# Laser_Array_CPU_V1_1.net
KiCad netlist of a schematic drawn in EAGLE
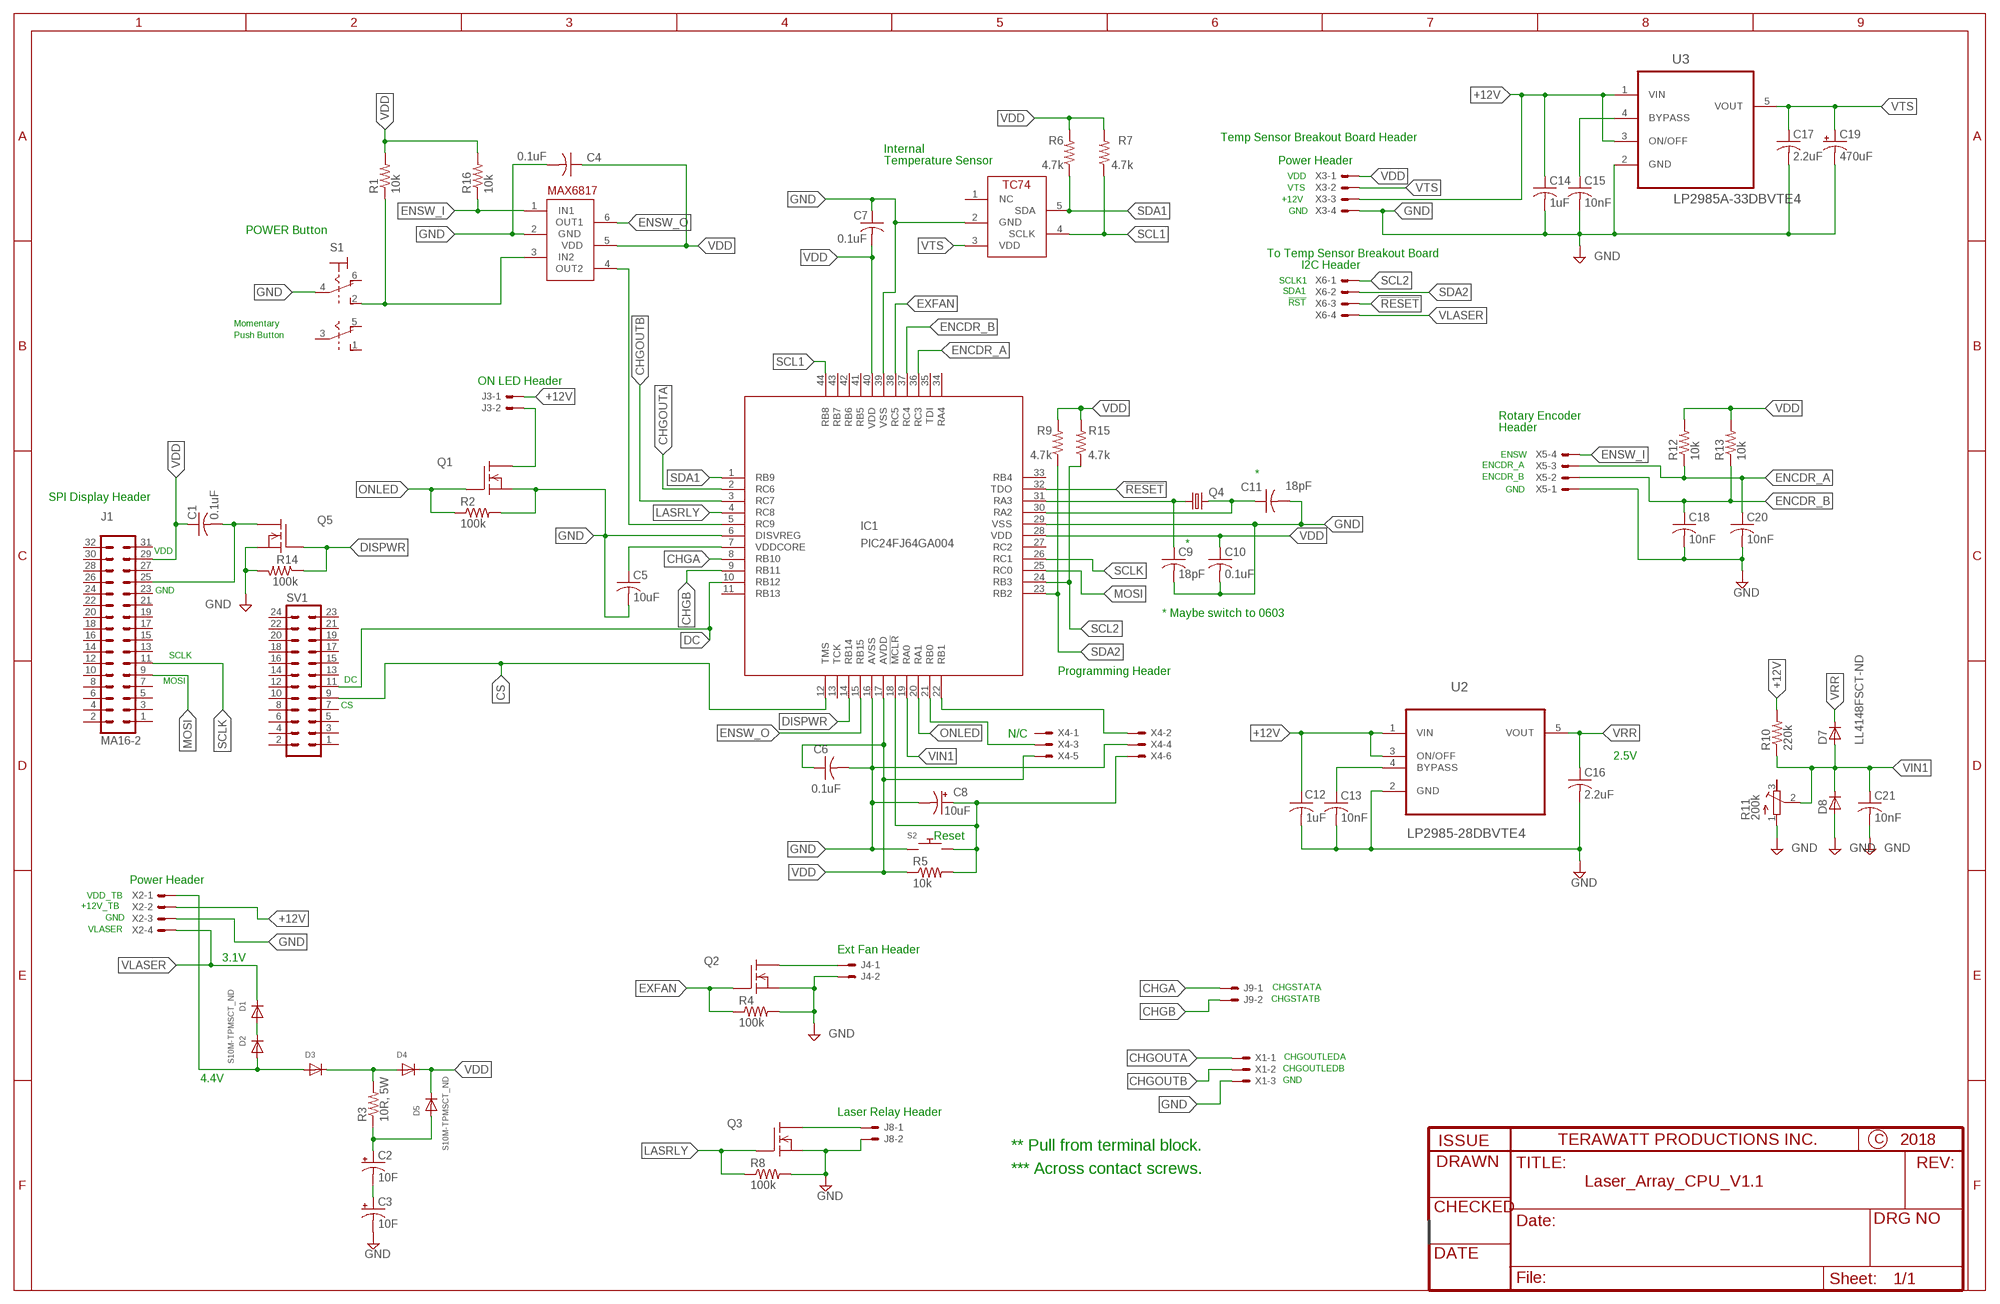
[diagram p0: schematic, sheet 1]

(export (version "E")
  (design (tool "Eeschema 10.0.6"))
  (components
    (comp (ref "C1")
      (value "0.1uF")
      (footprint "eagle-import:C0805")
      (libsource (lib "eagle-import") (part "C-USC0805"))
    )
    (comp (ref "C2")
      (value "10F")
      (footprint "eagle-import:E5-10,5")
      (libsource (lib "eagle-import") (part "CPOL-USE5-10.5"))
    )
    (comp (ref "C3")
      (value "10F")
      (footprint "eagle-import:E5-10,5")
      (libsource (lib "eagle-import") (part "CPOL-USE5-10.5"))
    )
    (comp (ref "C4")
      (value "0.1uF")
      (footprint "eagle-import:C0805")
      (libsource (lib "eagle-import") (part "C-USC0805"))
    )
    (comp (ref "C5")
      (value "10uF")
      (footprint "eagle-import:C0805")
      (libsource (lib "eagle-import") (part "C-USC0805"))
    )
    (comp (ref "C6")
      (value "0.1uF")
      (footprint "eagle-import:C0805")
      (libsource (lib "eagle-import") (part "C-USC0805"))
    )
    (comp (ref "C7")
      (value "0.1uF")
      (footprint "eagle-import:C0805")
      (libsource (lib "eagle-import") (part "C-USC0805"))
    )
    (comp (ref "C8")
      (value "10uF")
      (footprint "eagle-import:CAP3X3")
      (libsource (lib "eagle-import") (part "CAP3X3"))
    )
    (comp (ref "C9")
      (value "18pF")
      (footprint "eagle-import:C0805")
      (libsource (lib "eagle-import") (part "C-USC0805"))
    )
    (comp (ref "C10")
      (value "0.1uF")
      (footprint "eagle-import:C0805")
      (libsource (lib "eagle-import") (part "C-USC0805"))
    )
    (comp (ref "C11")
      (value "18pF")
      (footprint "eagle-import:C0805")
      (libsource (lib "eagle-import") (part "C-USC0805"))
    )
    (comp (ref "C12")
      (value "1uF")
      (footprint "eagle-import:C0805")
      (libsource (lib "eagle-import") (part "C-USC0805"))
    )
    (comp (ref "C13")
      (value "10nF")
      (footprint "eagle-import:C0805")
      (libsource (lib "eagle-import") (part "C-USC0805"))
    )
    (comp (ref "C14")
      (value "1uF")
      (footprint "eagle-import:C0805")
      (libsource (lib "eagle-import") (part "C-USC0805"))
    )
    (comp (ref "C15")
      (value "10nF")
      (footprint "eagle-import:C0805")
      (libsource (lib "eagle-import") (part "C-USC0805"))
    )
    (comp (ref "C16")
      (value "2.2uF")
      (footprint "eagle-import:C0805")
      (libsource (lib "eagle-import") (part "C-USC0805"))
    )
    (comp (ref "C17")
      (value "2.2uF")
      (footprint "eagle-import:C0805")
      (libsource (lib "eagle-import") (part "C-USC0805"))
    )
    (comp (ref "C18")
      (value "10nF")
      (footprint "eagle-import:C0805")
      (libsource (lib "eagle-import") (part "C-USC0805"))
    )
    (comp (ref "C19")
      (value "470uF")
      (footprint "eagle-import:PANASONIC_F")
      (libsource (lib "eagle-import") (part "CPOL-USF"))
    )
    (comp (ref "C20")
      (value "10nF")
      (footprint "eagle-import:C0805")
      (libsource (lib "eagle-import") (part "C-USC0805"))
    )
    (comp (ref "C21")
      (value "10nF")
      (footprint "eagle-import:C0805")
      (libsource (lib "eagle-import") (part "C-USC0805"))
    )
    (comp (ref "D1")
      (value "S10M-TPMSCT_ND")
      (footprint "eagle-import:S10M-TPMSCT-ND")
      (libsource (lib "eagle-import") (part "S10M-TPMSCT_ND"))
    )
    (comp (ref "D2")
      (value "641-1014-6-ND")
      (footprint "eagle-import:SOD-123")
      (libsource (lib "eagle-import") (part "DIODESOD-123"))
    )
    (comp (ref "D3")
      (value "641-1014-6-ND")
      (footprint "eagle-import:SOD-123")
      (libsource (lib "eagle-import") (part "DIODESOD-123"))
    )
    (comp (ref "D4")
      (value "641-1014-6-ND")
      (footprint "eagle-import:SOD-123")
      (libsource (lib "eagle-import") (part "DIODESOD-123"))
    )
    (comp (ref "D5")
      (value "S10M-TPMSCT_ND")
      (footprint "eagle-import:S10M-TPMSCT-ND")
      (libsource (lib "eagle-import") (part "S10M-TPMSCT_ND"))
    )
    (comp (ref "D7")
      (value "LL4148FSCT-ND")
      (footprint "eagle-import:SOD80")
      (libsource (lib "eagle-import") (part "D-SOD-80"))
    )
    (comp (ref "D8")
      (value "LL4148FSCT-ND")
      (footprint "eagle-import:SOD80")
      (libsource (lib "eagle-import") (part "D-SOD-80"))
    )
    (comp (ref "IC1")
      (value "PIC24FJ64GA004")
      (footprint "eagle-import:TQFP44")
      (fields (field (name "MPN") "PIC24FJ64GA004-E/PT"))
      (libsource (lib "eagle-import") (part "PIC24FJ64GA004"))
    )
    (comp (ref "J1")
      (value "MA16-2")
      (footprint "eagle-import:MA16-2")
      (libsource (lib "eagle-import") (part "MA16-2"))
    )
    (comp (ref "J3")
      (value "22-23-2021")
      (footprint "eagle-import:22-23-2021")
      (fields (field (name "MF") "MOLEX"))
      (libsource (lib "eagle-import") (part "22-23-2021"))
    )
    (comp (ref "J4")
      (value "22-23-2021")
      (footprint "eagle-import:22-23-2021")
      (fields (field (name "MF") "MOLEX"))
      (libsource (lib "eagle-import") (part "22-23-2021"))
    )
    (comp (ref "J8")
      (value "22-23-2021")
      (footprint "eagle-import:22-23-2021")
      (fields (field (name "MF") "MOLEX"))
      (libsource (lib "eagle-import") (part "22-23-2021"))
    )
    (comp (ref "J9")
      (value "22-23-2021")
      (footprint "eagle-import:22-23-2021")
      (fields (field (name "MF") "MOLEX"))
      (libsource (lib "eagle-import") (part "22-23-2021"))
    )
    (comp (ref "Q1")
      (value "QS5U34CT-ND_MOSFET_N_CHANNEL")
      (footprint "eagle-import:SOT23-5L")
      (libsource (lib "eagle-import") (part "QS5U34CT-ND_MOSFET_N_CHANNEL"))
    )
    (comp (ref "Q2")
      (value "QS5U34CT-ND_MOSFET_N_CHANNEL")
      (footprint "eagle-import:SOT23-5L")
      (libsource (lib "eagle-import") (part "QS5U34CT-ND_MOSFET_N_CHANNEL"))
    )
    (comp (ref "Q3")
      (value "QS5U34CT-ND_MOSFET_N_CHANNEL")
      (footprint "eagle-import:SOT23-5L")
      (libsource (lib "eagle-import") (part "QS5U34CT-ND_MOSFET_N_CHANNEL"))
    )
    (comp (ref "Q4")
      (value "CRYSTALSM49")
      (footprint "eagle-import:SM49")
      (libsource (lib "eagle-import") (part "CRYSTALSM49"))
    )
    (comp (ref "Q5")
      (value "QS5U34CT-ND_MOSFET_N_CHANNEL")
      (footprint "eagle-import:SOT23-5L")
      (libsource (lib "eagle-import") (part "QS5U34CT-ND_MOSFET_N_CHANNEL"))
    )
    (comp (ref "R1")
      (value "10k")
      (footprint "eagle-import:R0805")
      (libsource (lib "eagle-import") (part "R-US_R0805"))
    )
    (comp (ref "R2")
      (value "100k")
      (footprint "eagle-import:R0805")
      (libsource (lib "eagle-import") (part "R-US_R0805"))
    )
    (comp (ref "R3")
      (value "10R, 5W")
      (footprint "eagle-import:RESISTOR5W")
      (libsource (lib "eagle-import") (part "RESISTOR5W"))
    )
    (comp (ref "R4")
      (value "100k")
      (footprint "eagle-import:R0805")
      (libsource (lib "eagle-import") (part "R-US_R0805"))
    )
    (comp (ref "R5")
      (value "10k")
      (footprint "eagle-import:R0805")
      (libsource (lib "eagle-import") (part "R-US_R0805"))
    )
    (comp (ref "R6")
      (value "4.7k")
      (footprint "eagle-import:M0805")
      (libsource (lib "eagle-import") (part "R-US_M0805"))
    )
    (comp (ref "R7")
      (value "4.7k")
      (footprint "eagle-import:M0805")
      (libsource (lib "eagle-import") (part "R-US_M0805"))
    )
    (comp (ref "R8")
      (value "100k")
      (footprint "eagle-import:R0805")
      (libsource (lib "eagle-import") (part "R-US_R0805"))
    )
    (comp (ref "R9")
      (value "4.7k")
      (footprint "eagle-import:M0805")
      (libsource (lib "eagle-import") (part "R-US_M0805"))
    )
    (comp (ref "R10")
      (value "220k")
      (footprint "eagle-import:M0805")
      (libsource (lib "eagle-import") (part "R-US_M0805"))
    )
    (comp (ref "R11")
      (value "200k")
      (footprint "eagle-import:RTRIM3224X")
      (libsource (lib "eagle-import") (part "R-TRIMM3224X"))
    )
    (comp (ref "R12")
      (value "10k")
      (footprint "eagle-import:M0805")
      (libsource (lib "eagle-import") (part "R-US_M0805"))
    )
    (comp (ref "R13")
      (value "10k")
      (footprint "eagle-import:M0805")
      (libsource (lib "eagle-import") (part "R-US_M0805"))
    )
    (comp (ref "R14")
      (value "100k")
      (footprint "eagle-import:R0805")
      (libsource (lib "eagle-import") (part "R-US_R0805"))
    )
    (comp (ref "R15")
      (value "4.7k")
      (footprint "eagle-import:M0805")
      (libsource (lib "eagle-import") (part "R-US_M0805"))
    )
    (comp (ref "R16")
      (value "10k")
      (footprint "eagle-import:R0805")
      (libsource (lib "eagle-import") (part "R-US_R0805"))
    )
    (comp (ref "S1")
      (value "DPDT_TOGGLE")
      (footprint "eagle-import:22-23-2061")
      (libsource (lib "eagle-import") (part "DPDT_TOGGLE"))
    )
    (comp (ref "S2")
      (value "TACT_PB")
      (footprint "eagle-import:PUSHBUTTON_SMD_SJ")
      (libsource (lib "eagle-import") (part "TACT_PB"))
    )
    (comp (ref "S3")
      (value "TC74")
      (footprint "eagle-import:SOT23-5L")
      (libsource (lib "eagle-import") (part "TC74"))
    )
    (comp (ref "SV1")
      (value "MA12-2")
      (footprint "eagle-import:MA12-2")
      (libsource (lib "eagle-import") (part "MA12-2"))
    )
    (comp (ref "U1")
      (value "MAX6817")
      (footprint "eagle-import:SOT23-6")
      (libsource (lib "eagle-import") (part "MAX6817"))
    )
    (comp (ref "U2")
      (value "LP2985-28DBVTE4")
      (footprint "eagle-import:SOT95P280X145-5N")
      (libsource (lib "eagle-import") (part "LP2985-28DBVTE4"))
    )
    (comp (ref "U3")
      (value "LP2985A-33DBVTE4")
      (footprint "eagle-import:SOT95P280X145-5N")
      (libsource (lib "eagle-import") (part "LP2985A-33DBVTE4"))
    )
    (comp (ref "X1")
      (value "22-23-2031")
      (footprint "eagle-import:22-23-2031")
      (fields (field (name "MF") "MOLEX"))
      (libsource (lib "eagle-import") (part "22-23-2031"))
    )
    (comp (ref "X2")
      (value "22-23-2041")
      (footprint "eagle-import:22-23-2041")
      (fields (field (name "MF") "MOLEX"))
      (libsource (lib "eagle-import") (part "22-23-2041"))
    )
    (comp (ref "X3")
      (value "22-23-2041")
      (footprint "eagle-import:22-23-2041")
      (fields (field (name "MF") "MOLEX"))
      (libsource (lib "eagle-import") (part "22-23-2041"))
    )
    (comp (ref "X4")
      (value "87758-0616")
      (footprint "eagle-import:87758-0616")
      (libsource (lib "eagle-import") (part "87758-0616"))
    )
    (comp (ref "X5")
      (value "22-23-2041")
      (footprint "eagle-import:22-23-2041")
      (fields (field (name "MF") "MOLEX"))
      (libsource (lib "eagle-import") (part "22-23-2041"))
    )
    (comp (ref "X6")
      (value "22-23-2041")
      (footprint "eagle-import:22-23-2041")
      (fields (field (name "MF") "MOLEX"))
      (libsource (lib "eagle-import") (part "22-23-2041"))
    )
  )
  (nets
    (net (code "1") (name "+12V") (class "Default")
      (node (ref "C12") (pin "1") (pinfunction "1_1") (pintype "passive"))
      (node (ref "C14") (pin "1") (pinfunction "1_1") (pintype "passive"))
      (node (ref "J3") (pin "1") (pinfunction "S_1") (pintype "passive"))
      (node (ref "R10") (pin "2") (pinfunction "2_2") (pintype "passive"))
      (node (ref "U2") (pin "1") (pinfunction "VIN_1") (pintype "power_in"))
      (node (ref "U2") (pin "3") (pinfunction "ON/OFF_3") (pintype "input"))
      (node (ref "U3") (pin "1") (pinfunction "VIN_1") (pintype "power_in"))
      (node (ref "U3") (pin "3") (pinfunction "ON/OFF_3") (pintype "input"))
      (node (ref "X2") (pin "2") (pinfunction "S_2") (pintype "passive"))
      (node (ref "X3") (pin "3") (pinfunction "S_3") (pintype "passive"))
    )
    (net (code "2") (name "/~{RESET}") (class "Default")
      (node (ref "IC1") (pin "32") (pinfunction "TDO_32") (pintype "output"))
      (node (ref "X6") (pin "3") (pinfunction "S_3") (pintype "passive"))
    )
    (net (code "3") (name "CHGA") (class "Default")
      (node (ref "IC1") (pin "8") (pinfunction "RB10_8") (pintype "bidirectional"))
      (node (ref "J9") (pin "1") (pinfunction "S_1") (pintype "passive"))
    )
    (net (code "4") (name "CHGB") (class "Default")
      (node (ref "IC1") (pin "9") (pinfunction "RB11_9") (pintype "bidirectional"))
      (node (ref "J9") (pin "2") (pinfunction "S_2") (pintype "passive"))
    )
    (net (code "5") (name "CHGOUTA") (class "Default")
      (node (ref "IC1") (pin "2") (pinfunction "RC6_2") (pintype "bidirectional"))
      (node (ref "X1") (pin "1") (pinfunction "S_1") (pintype "passive"))
    )
    (net (code "6") (name "CHGOUTB") (class "Default")
      (node (ref "IC1") (pin "3") (pinfunction "RC7_3") (pintype "bidirectional"))
      (node (ref "X1") (pin "2") (pinfunction "S_2") (pintype "passive"))
    )
    (net (code "7") (name "CS") (class "Default")
      (node (ref "IC1") (pin "12") (pinfunction "TMS_12") (pintype "input"))
      (node (ref "SV1") (pin "9") (pinfunction "9_9") (pintype "passive"))
    )
    (net (code "8") (name "DC") (class "Default")
      (node (ref "IC1") (pin "10") (pinfunction "RB12_10") (pintype "bidirectional"))
      (node (ref "SV1") (pin "11") (pinfunction "11_11") (pintype "passive"))
    )
    (net (code "9") (name "DISPWR") (class "Default")
      (node (ref "IC1") (pin "14") (pinfunction "RB14_14") (pintype "bidirectional"))
      (node (ref "Q5") (pin "1") (pinfunction "G_1") (pintype "passive"))
      (node (ref "R14") (pin "1") (pinfunction "1_1") (pintype "passive"))
    )
    (net (code "10") (name "ENCDR_A") (class "Default")
      (node (ref "C20") (pin "1") (pinfunction "1_1") (pintype "passive"))
      (node (ref "IC1") (pin "36") (pinfunction "RC3_36") (pintype "bidirectional"))
      (node (ref "R12") (pin "1") (pinfunction "1_1") (pintype "passive"))
      (node (ref "X5") (pin "3") (pinfunction "S_3") (pintype "passive"))
    )
    (net (code "11") (name "ENCDR_B") (class "Default")
      (node (ref "C18") (pin "1") (pinfunction "1_1") (pintype "passive"))
      (node (ref "IC1") (pin "37") (pinfunction "RC4_37") (pintype "bidirectional"))
      (node (ref "R13") (pin "1") (pinfunction "1_1") (pintype "passive"))
      (node (ref "X5") (pin "2") (pinfunction "S_2") (pintype "passive"))
    )
    (net (code "12") (name "ENSW_I") (class "Default")
      (node (ref "R16") (pin "1") (pinfunction "1_1") (pintype "passive"))
      (node (ref "U1") (pin "1") (pinfunction "IN1_1") (pintype "input"))
      (node (ref "X5") (pin "4") (pinfunction "S_4") (pintype "passive"))
    )
    (net (code "13") (name "ENSW_O") (class "Default")
      (node (ref "IC1") (pin "15") (pinfunction "RB15_15") (pintype "bidirectional"))
      (node (ref "U1") (pin "6") (pinfunction "OUT1_6") (pintype "output"))
    )
    (net (code "14") (name "EXFAN") (class "Default")
      (node (ref "IC1") (pin "38") (pinfunction "RC5_38") (pintype "bidirectional"))
      (node (ref "Q2") (pin "1") (pinfunction "G_1") (pintype "passive"))
      (node (ref "R4") (pin "1") (pinfunction "1_1") (pintype "passive"))
    )
    (net (code "15") (name "GND") (class "Default")
      (node (ref "C10") (pin "2") (pinfunction "2_2") (pintype "passive"))
      (node (ref "C11") (pin "2") (pinfunction "2_2") (pintype "passive"))
      (node (ref "C12") (pin "2") (pinfunction "2_2") (pintype "passive"))
      (node (ref "C13") (pin "2") (pinfunction "2_2") (pintype "passive"))
      (node (ref "C14") (pin "2") (pinfunction "2_2") (pintype "passive"))
      (node (ref "C15") (pin "2") (pinfunction "2_2") (pintype "passive"))
      (node (ref "C16") (pin "2") (pinfunction "2_2") (pintype "passive"))
      (node (ref "C17") (pin "2") (pinfunction "2_2") (pintype "passive"))
      (node (ref "C18") (pin "2") (pinfunction "2_2") (pintype "passive"))
      (node (ref "C19") (pin "-") (pinfunction "-_-") (pintype "passive"))
      (node (ref "C20") (pin "2") (pinfunction "2_2") (pintype "passive"))
      (node (ref "C21") (pin "2") (pinfunction "2_2") (pintype "passive"))
      (node (ref "C3") (pin "-") (pinfunction "-_-") (pintype "passive"))
      (node (ref "C4") (pin "2") (pinfunction "2_2") (pintype "passive"))
      (node (ref "C5") (pin "2") (pinfunction "2_2") (pintype "passive"))
      (node (ref "C6") (pin "2") (pinfunction "2_2") (pintype "passive"))
      (node (ref "C7") (pin "1") (pinfunction "1_1") (pintype "passive"))
      (node (ref "C8") (pin "-") (pinfunction "-_-") (pintype "passive"))
      (node (ref "C9") (pin "2") (pinfunction "2_2") (pintype "passive"))
      (node (ref "D8") (pin "2") (pinfunction "A_2") (pintype "passive"))
      (node (ref "IC1") (pin "16") (pinfunction "AVSS_16") (pintype "power_in"))
      (node (ref "IC1") (pin "29") (pinfunction "VSS_29") (pintype "power_in"))
      (node (ref "IC1") (pin "39") (pinfunction "VSS_39") (pintype "power_in"))
      (node (ref "IC1") (pin "6") (pinfunction "DISVREG_6") (pintype "passive"))
      (node (ref "J4") (pin "2") (pinfunction "S_2") (pintype "passive"))
      (node (ref "J8") (pin "2") (pinfunction "S_2") (pintype "passive"))
      (node (ref "Q1") (pin "2") (pinfunction "S_2") (pintype "passive"))
      (node (ref "Q2") (pin "2") (pinfunction "S_2") (pintype "passive"))
      (node (ref "Q3") (pin "2") (pinfunction "S_2") (pintype "passive"))
      (node (ref "Q5") (pin "2") (pinfunction "S_2") (pintype "passive"))
      (node (ref "R11") (pin "1") (pinfunction "A_1") (pintype "passive"))
      (node (ref "R14") (pin "2") (pinfunction "2_2") (pintype "passive"))
      (node (ref "R2") (pin "2") (pinfunction "2_2") (pintype "passive"))
      (node (ref "R4") (pin "2") (pinfunction "2_2") (pintype "passive"))
      (node (ref "R8") (pin "2") (pinfunction "2_2") (pintype "passive"))
      (node (ref "S1") (pin "4") (pinfunction "P_4") (pintype "passive"))
      (node (ref "S2") (pin "1") (pinfunction "1_1") (pintype "passive"))
      (node (ref "S2") (pin "2") (pinfunction "1_2") (pintype "passive"))
      (node (ref "S3") (pin "2") (pinfunction "GND_2") (pintype "bidirectional"))
      (node (ref "U1") (pin "2") (pinfunction "GND_2") (pintype "power_in"))
      (node (ref "U2") (pin "2") (pinfunction "GND_2") (pintype "passive"))
      (node (ref "U3") (pin "2") (pinfunction "GND_2") (pintype "passive"))
      (node (ref "X1") (pin "3") (pinfunction "S_3") (pintype "passive"))
      (node (ref "X2") (pin "3") (pinfunction "S_3") (pintype "passive"))
      (node (ref "X3") (pin "4") (pinfunction "S_4") (pintype "passive"))
      (node (ref "X4") (pin "4") (pinfunction "S_4") (pintype "passive"))
      (node (ref "X5") (pin "1") (pinfunction "S_1") (pintype "passive"))
    )
    (net (code "16") (name "LASRLY") (class "Default")
      (node (ref "IC1") (pin "4") (pinfunction "RC8_4") (pintype "bidirectional"))
      (node (ref "Q3") (pin "1") (pinfunction "G_1") (pintype "passive"))
      (node (ref "R8") (pin "1") (pinfunction "1_1") (pintype "passive"))
    )
    (net (code "17") (name "MOSI") (class "Default")
      (node (ref "IC1") (pin "25") (pinfunction "RC0_25") (pintype "bidirectional"))
      (node (ref "J1") (pin "9") (pinfunction "9_9") (pintype "passive"))
    )
    (net (code "18") (name "Net-(C2-Pad+)") (class "Default")
      (node (ref "C2") (pin "+") (pinfunction "+_+") (pintype "passive"))
      (node (ref "D5") (pin "A") (pinfunction "A_A") (pintype "passive"))
      (node (ref "R3") (pin "1") (pinfunction "1_1") (pintype "passive"))
    )
    (net (code "19") (name "Net-(C2-Pad-)") (class "Default")
      (node (ref "C2") (pin "-") (pinfunction "-_-") (pintype "passive"))
      (node (ref "C3") (pin "+") (pinfunction "+_+") (pintype "passive"))
    )
    (net (code "20") (name "Net-(D1-PadA)") (class "Default")
      (node (ref "D1") (pin "A") (pinfunction "A_A") (pintype "passive"))
      (node (ref "D2") (pin "C") (pinfunction "C_C") (pintype "passive"))
    )
    (net (code "21") (name "Net-(D3-PadC)") (class "Default")
      (node (ref "D3") (pin "C") (pinfunction "C_C") (pintype "passive"))
      (node (ref "D4") (pin "A") (pinfunction "A_A") (pintype "passive"))
      (node (ref "R3") (pin "2") (pinfunction "2_2") (pintype "passive"))
    )
    (net (code "22") (name "Net-(IC1-RA2)") (class "Default")
      (node (ref "C11") (pin "1") (pinfunction "1_1") (pintype "passive"))
      (node (ref "IC1") (pin "30") (pinfunction "RA2_30") (pintype "bidirectional"))
      (node (ref "Q4") (pin "2") (pinfunction "2_2") (pintype "passive"))
    )
    (net (code "23") (name "Net-(IC1-RA3)") (class "Default")
      (node (ref "C9") (pin "1") (pinfunction "1_1") (pintype "passive"))
      (node (ref "IC1") (pin "31") (pinfunction "RA3_31") (pintype "bidirectional"))
      (node (ref "Q4") (pin "1") (pinfunction "1_1") (pintype "passive"))
    )
    (net (code "24") (name "Net-(IC1-RB0)") (class "Default")
      (node (ref "IC1") (pin "21") (pinfunction "RB0_21") (pintype "bidirectional"))
      (node (ref "X4") (pin "3") (pinfunction "S_3") (pintype "passive"))
    )
    (net (code "25") (name "Net-(IC1-RB1)") (class "Default")
      (node (ref "IC1") (pin "22") (pinfunction "RB1_22") (pintype "bidirectional"))
      (node (ref "X4") (pin "2") (pinfunction "S_2") (pintype "passive"))
    )
    (net (code "26") (name "Net-(IC1-RC9)") (class "Default")
      (node (ref "IC1") (pin "5") (pinfunction "RC9_5") (pintype "bidirectional"))
      (node (ref "U1") (pin "4") (pinfunction "OUT2_4") (pintype "output"))
    )
    (net (code "27") (name "Net-(IC1-VDDCORE)") (class "Default")
      (node (ref "C5") (pin "1") (pinfunction "1_1") (pintype "passive"))
      (node (ref "IC1") (pin "7") (pinfunction "VDDCORE_7") (pintype "power_in"))
    )
    (net (code "28") (name "Net-(IC1-~{MCLR})") (class "Default")
      (node (ref "C8") (pin "+") (pinfunction "+_+") (pintype "passive"))
      (node (ref "IC1") (pin "18") (pinfunction "~{MCLR}_18") (pintype "bidirectional"))
      (node (ref "R5") (pin "2") (pinfunction "2_2") (pintype "passive"))
      (node (ref "S2") (pin "3") (pinfunction "2_3") (pintype "passive"))
      (node (ref "S2") (pin "4") (pinfunction "2_4") (pintype "passive"))
      (node (ref "X4") (pin "6") (pinfunction "S_6") (pintype "passive"))
    )
    (net (code "29") (name "Net-(J3B-S)") (class "Default")
      (node (ref "J3") (pin "2") (pinfunction "S_2") (pintype "passive"))
      (node (ref "Q1") (pin "5") (pinfunction "D_5") (pintype "passive"))
    )
    (net (code "30") (name "Net-(J4A-S)") (class "Default")
      (node (ref "J4") (pin "1") (pinfunction "S_1") (pintype "passive"))
      (node (ref "Q2") (pin "5") (pinfunction "D_5") (pintype "passive"))
    )
    (net (code "31") (name "Net-(J8A-S)") (class "Default")
      (node (ref "J8") (pin "1") (pinfunction "S_1") (pintype "passive"))
      (node (ref "Q3") (pin "5") (pinfunction "D_5") (pintype "passive"))
    )
    (net (code "32") (name "Net-(Q5-D)") (class "Default")
      (node (ref "C1") (pin "2") (pinfunction "2_2") (pintype "passive"))
      (node (ref "J1") (pin "25") (pinfunction "25_25") (pintype "passive"))
      (node (ref "Q5") (pin "5") (pinfunction "D_5") (pintype "passive"))
    )
    (net (code "33") (name "Net-(S1-S)") (class "Default")
      (node (ref "R1") (pin "1") (pinfunction "1_1") (pintype "passive"))
      (node (ref "S1") (pin "2") (pinfunction "S_2") (pintype "passive"))
      (node (ref "U1") (pin "3") (pinfunction "IN2_3") (pintype "input"))
    )
    (net (code "34") (name "Net-(U2-BYPASS)") (class "Default")
      (node (ref "C13") (pin "1") (pinfunction "1_1") (pintype "passive"))
      (node (ref "U2") (pin "4") (pinfunction "BYPASS_4") (pintype "input"))
    )
    (net (code "35") (name "Net-(U3-BYPASS)") (class "Default")
      (node (ref "C15") (pin "1") (pinfunction "1_1") (pintype "passive"))
      (node (ref "U3") (pin "4") (pinfunction "BYPASS_4") (pintype "input"))
    )
    (net (code "36") (name "Net-(X2A-S)") (class "Default")
      (node (ref "D2") (pin "A") (pinfunction "A_A") (pintype "passive"))
      (node (ref "D3") (pin "A") (pinfunction "A_A") (pintype "passive"))
      (node (ref "X2") (pin "1") (pinfunction "S_1") (pintype "passive"))
    )
    (net (code "37") (name "ONLED") (class "Default")
      (node (ref "IC1") (pin "20") (pinfunction "RA1_20") (pintype "bidirectional"))
      (node (ref "Q1") (pin "1") (pinfunction "G_1") (pintype "passive"))
      (node (ref "R2") (pin "1") (pinfunction "1_1") (pintype "passive"))
    )
    (net (code "38") (name "SCL1") (class "Default")
      (node (ref "IC1") (pin "44") (pinfunction "RB8_44") (pintype "bidirectional"))
      (node (ref "R7") (pin "1") (pinfunction "1_1") (pintype "passive"))
      (node (ref "S3") (pin "4") (pinfunction "SCLK_4") (pintype "bidirectional"))
    )
    (net (code "39") (name "SCL2") (class "Default")
      (node (ref "IC1") (pin "24") (pinfunction "RB3_24") (pintype "bidirectional"))
      (node (ref "R15") (pin "1") (pinfunction "1_1") (pintype "passive"))
      (node (ref "X6") (pin "1") (pinfunction "S_1") (pintype "passive"))
    )
    (net (code "40") (name "SCLK") (class "Default")
      (node (ref "IC1") (pin "26") (pinfunction "RC1_26") (pintype "bidirectional"))
      (node (ref "J1") (pin "11") (pinfunction "11_11") (pintype "passive"))
    )
    (net (code "41") (name "SDA1") (class "Default")
      (node (ref "IC1") (pin "1") (pinfunction "RB9_1") (pintype "bidirectional"))
      (node (ref "R6") (pin "1") (pinfunction "1_1") (pintype "passive"))
      (node (ref "S3") (pin "5") (pinfunction "SDA_5") (pintype "bidirectional"))
    )
    (net (code "42") (name "SDA2") (class "Default")
      (node (ref "IC1") (pin "23") (pinfunction "RB2_23") (pintype "bidirectional"))
      (node (ref "R9") (pin "1") (pinfunction "1_1") (pintype "passive"))
      (node (ref "X6") (pin "2") (pinfunction "S_2") (pintype "passive"))
    )
    (net (code "43") (name "VDD") (class "Default")
      (node (ref "C1") (pin "1") (pinfunction "1_1") (pintype "passive"))
      (node (ref "C10") (pin "1") (pinfunction "1_1") (pintype "passive"))
      (node (ref "C4") (pin "1") (pinfunction "1_1") (pintype "passive"))
      (node (ref "C6") (pin "1") (pinfunction "1_1") (pintype "passive"))
      (node (ref "C7") (pin "2") (pinfunction "2_2") (pintype "passive"))
      (node (ref "D4") (pin "C") (pinfunction "C_C") (pintype "passive"))
      (node (ref "D5") (pin "C") (pinfunction "C_C") (pintype "passive"))
      (node (ref "IC1") (pin "17") (pinfunction "AVDD_17") (pintype "power_in"))
      (node (ref "IC1") (pin "28") (pinfunction "VDD_28") (pintype "power_in"))
      (node (ref "IC1") (pin "40") (pinfunction "VDD_40") (pintype "power_in"))
      (node (ref "J1") (pin "29") (pinfunction "29_29") (pintype "passive"))
      (node (ref "R1") (pin "2") (pinfunction "2_2") (pintype "passive"))
      (node (ref "R12") (pin "2") (pinfunction "2_2") (pintype "passive"))
      (node (ref "R13") (pin "2") (pinfunction "2_2") (pintype "passive"))
      (node (ref "R15") (pin "2") (pinfunction "2_2") (pintype "passive"))
      (node (ref "R16") (pin "2") (pinfunction "2_2") (pintype "passive"))
      (node (ref "R5") (pin "1") (pinfunction "1_1") (pintype "passive"))
      (node (ref "R6") (pin "2") (pinfunction "2_2") (pintype "passive"))
      (node (ref "R7") (pin "2") (pinfunction "2_2") (pintype "passive"))
      (node (ref "R9") (pin "2") (pinfunction "2_2") (pintype "passive"))
      (node (ref "U1") (pin "5") (pinfunction "VDD_5") (pintype "power_in"))
      (node (ref "X3") (pin "1") (pinfunction "S_1") (pintype "passive"))
      (node (ref "X4") (pin "5") (pinfunction "S_5") (pintype "passive"))
    )
    (net (code "44") (name "VIN1") (class "Default")
      (node (ref "C21") (pin "1") (pinfunction "1_1") (pintype "passive"))
      (node (ref "D7") (pin "2") (pinfunction "A_2") (pintype "passive"))
      (node (ref "D8") (pin "1") (pinfunction "C_1") (pintype "passive"))
      (node (ref "IC1") (pin "19") (pinfunction "RA0_19") (pintype "bidirectional"))
      (node (ref "R10") (pin "1") (pinfunction "1_1") (pintype "passive"))
      (node (ref "R11") (pin "2") (pinfunction "S_2") (pintype "passive"))
    )
    (net (code "45") (name "VLASER") (class "Default")
      (node (ref "D1") (pin "C") (pinfunction "C_C") (pintype "passive"))
      (node (ref "X2") (pin "4") (pinfunction "S_4") (pintype "passive"))
      (node (ref "X6") (pin "4") (pinfunction "S_4") (pintype "passive"))
    )
    (net (code "46") (name "VRR") (class "Default")
      (node (ref "C16") (pin "1") (pinfunction "1_1") (pintype "passive"))
      (node (ref "D7") (pin "1") (pinfunction "C_1") (pintype "passive"))
      (node (ref "U2") (pin "5") (pinfunction "VOUT_5") (pintype "output"))
    )
    (net (code "47") (name "VTS") (class "Default")
      (node (ref "C17") (pin "1") (pinfunction "1_1") (pintype "passive"))
      (node (ref "C19") (pin "+") (pinfunction "+_+") (pintype "passive"))
      (node (ref "S3") (pin "3") (pinfunction "VDD_3") (pintype "bidirectional"))
      (node (ref "U3") (pin "5") (pinfunction "VOUT_5") (pintype "output"))
      (node (ref "X3") (pin "2") (pinfunction "S_2") (pintype "passive"))
    )
    (net (code "48") (name "unconnected-(IC1-RA4-Pad34)") (class "Default")
      (node (ref "IC1") (pin "34") (pinfunction "RA4_34") (pintype "bidirectional"))
    )
    (net (code "49") (name "unconnected-(IC1-RB4-Pad33)") (class "Default")
      (node (ref "IC1") (pin "33") (pinfunction "RB4_33") (pintype "bidirectional"))
    )
    (net (code "50") (name "unconnected-(IC1-RB5-Pad41)") (class "Default")
      (node (ref "IC1") (pin "41") (pinfunction "RB5_41") (pintype "bidirectional"))
    )
    (net (code "51") (name "unconnected-(IC1-RB6-Pad42)") (class "Default")
      (node (ref "IC1") (pin "42") (pinfunction "RB6_42") (pintype "bidirectional"))
    )
    (net (code "52") (name "unconnected-(IC1-RB7-Pad43)") (class "Default")
      (node (ref "IC1") (pin "43") (pinfunction "RB7_43") (pintype "bidirectional"))
    )
    (net (code "53") (name "unconnected-(IC1-RB13-Pad11)") (class "Default")
      (node (ref "IC1") (pin "11") (pinfunction "RB13_11") (pintype "bidirectional"))
    )
    (net (code "54") (name "unconnected-(IC1-RC2-Pad27)") (class "Default")
      (node (ref "IC1") (pin "27") (pinfunction "RC2_27") (pintype "bidirectional"))
    )
    (net (code "55") (name "unconnected-(IC1-TCK-Pad13)") (class "Default")
      (node (ref "IC1") (pin "13") (pinfunction "TCK_13") (pintype "input"))
    )
    (net (code "56") (name "unconnected-(IC1-TDI-Pad35)") (class "Default")
      (node (ref "IC1") (pin "35") (pinfunction "TDI_35") (pintype "input"))
    )
    (net (code "57") (name "unconnected-(J1-Pad1)") (class "Default")
      (node (ref "J1") (pin "1") (pinfunction "1_1") (pintype "passive"))
    )
    (net (code "58") (name "unconnected-(J1-Pad2)") (class "Default")
      (node (ref "J1") (pin "2") (pinfunction "2_2") (pintype "passive"))
    )
    (net (code "59") (name "unconnected-(J1-Pad3)") (class "Default")
      (node (ref "J1") (pin "3") (pinfunction "3_3") (pintype "passive"))
    )
    (net (code "60") (name "unconnected-(J1-Pad4)") (class "Default")
      (node (ref "J1") (pin "4") (pinfunction "4_4") (pintype "passive"))
    )
    (net (code "61") (name "unconnected-(J1-Pad5)") (class "Default")
      (node (ref "J1") (pin "5") (pinfunction "5_5") (pintype "passive"))
    )
    (net (code "62") (name "unconnected-(J1-Pad6)") (class "Default")
      (node (ref "J1") (pin "6") (pinfunction "6_6") (pintype "passive"))
    )
    (net (code "63") (name "unconnected-(J1-Pad7)") (class "Default")
      (node (ref "J1") (pin "7") (pinfunction "7_7") (pintype "passive"))
    )
    (net (code "64") (name "unconnected-(J1-Pad8)") (class "Default")
      (node (ref "J1") (pin "8") (pinfunction "8_8") (pintype "passive"))
    )
    (net (code "65") (name "unconnected-(J1-Pad10)") (class "Default")
      (node (ref "J1") (pin "10") (pinfunction "10_10") (pintype "passive"))
    )
    (net (code "66") (name "unconnected-(J1-Pad12)") (class "Default")
      (node (ref "J1") (pin "12") (pinfunction "12_12") (pintype "passive"))
    )
    (net (code "67") (name "unconnected-(J1-Pad13)") (class "Default")
      (node (ref "J1") (pin "13") (pinfunction "13_13") (pintype "passive"))
    )
    (net (code "68") (name "unconnected-(J1-Pad14)") (class "Default")
      (node (ref "J1") (pin "14") (pinfunction "14_14") (pintype "passive"))
    )
    (net (code "69") (name "unconnected-(J1-Pad15)") (class "Default")
      (node (ref "J1") (pin "15") (pinfunction "15_15") (pintype "passive"))
    )
    (net (code "70") (name "unconnected-(J1-Pad16)") (class "Default")
      (node (ref "J1") (pin "16") (pinfunction "16_16") (pintype "passive"))
    )
    (net (code "71") (name "unconnected-(J1-Pad17)") (class "Default")
      (node (ref "J1") (pin "17") (pinfunction "17_17") (pintype "passive"))
    )
    (net (code "72") (name "unconnected-(J1-Pad18)") (class "Default")
      (node (ref "J1") (pin "18") (pinfunction "18_18") (pintype "passive"))
    )
    (net (code "73") (name "unconnected-(J1-Pad19)") (class "Default")
      (node (ref "J1") (pin "19") (pinfunction "19_19") (pintype "passive"))
    )
    (net (code "74") (name "unconnected-(J1-Pad20)") (class "Default")
      (node (ref "J1") (pin "20") (pinfunction "20_20") (pintype "passive"))
    )
    (net (code "75") (name "unconnected-(J1-Pad21)") (class "Default")
      (node (ref "J1") (pin "21") (pinfunction "21_21") (pintype "passive"))
    )
    (net (code "76") (name "unconnected-(J1-Pad22)") (class "Default")
      (node (ref "J1") (pin "22") (pinfunction "22_22") (pintype "passive"))
    )
    (net (code "77") (name "unconnected-(J1-Pad23)") (class "Default")
      (node (ref "J1") (pin "23") (pinfunction "23_23") (pintype "passive"))
    )
    (net (code "78") (name "unconnected-(J1-Pad24)") (class "Default")
      (node (ref "J1") (pin "24") (pinfunction "24_24") (pintype "passive"))
    )
    (net (code "79") (name "unconnected-(J1-Pad26)") (class "Default")
      (node (ref "J1") (pin "26") (pinfunction "26_26") (pintype "passive"))
    )
    (net (code "80") (name "unconnected-(J1-Pad27)") (class "Default")
      (node (ref "J1") (pin "27") (pinfunction "27_27") (pintype "passive"))
    )
    (net (code "81") (name "unconnected-(J1-Pad28)") (class "Default")
      (node (ref "J1") (pin "28") (pinfunction "28_28") (pintype "passive"))
    )
    (net (code "82") (name "unconnected-(J1-Pad30)") (class "Default")
      (node (ref "J1") (pin "30") (pinfunction "30_30") (pintype "passive"))
    )
    (net (code "83") (name "unconnected-(J1-Pad31)") (class "Default")
      (node (ref "J1") (pin "31") (pinfunction "31_31") (pintype "passive"))
    )
    (net (code "84") (name "unconnected-(J1-Pad32)") (class "Default")
      (node (ref "J1") (pin "32") (pinfunction "32_32") (pintype "passive"))
    )
    (net (code "85") (name "unconnected-(R11-E-Pad3)") (class "Default")
      (node (ref "R11") (pin "3") (pinfunction "E_3") (pintype "passive"))
    )
    (net (code "86") (name "unconnected-(S1-O-Pad6)") (class "Default")
      (node (ref "S1") (pin "6") (pinfunction "O_6") (pintype "passive"))
    )
    (net (code "87") (name "unconnected-(S1-O1-Pad5)") (class "Default")
      (node (ref "S1") (pin "5") (pinfunction "O1_5") (pintype "passive"))
    )
    (net (code "88") (name "unconnected-(S1-P1-Pad3)") (class "Default")
      (node (ref "S1") (pin "3") (pinfunction "P1_3") (pintype "passive"))
    )
    (net (code "89") (name "unconnected-(S1-S1-Pad1)") (class "Default")
      (node (ref "S1") (pin "1") (pinfunction "S1_1") (pintype "passive"))
    )
    (net (code "90") (name "unconnected-(S3-NC-Pad1)") (class "Default")
      (node (ref "S3") (pin "1") (pinfunction "NC_1") (pintype "bidirectional"))
    )
    (net (code "91") (name "unconnected-(SV1-Pad1)") (class "Default")
      (node (ref "SV1") (pin "1") (pinfunction "1_1") (pintype "passive"))
    )
    (net (code "92") (name "unconnected-(SV1-Pad2)") (class "Default")
      (node (ref "SV1") (pin "2") (pinfunction "2_2") (pintype "passive"))
    )
    (net (code "93") (name "unconnected-(SV1-Pad3)") (class "Default")
      (node (ref "SV1") (pin "3") (pinfunction "3_3") (pintype "passive"))
    )
    (net (code "94") (name "unconnected-(SV1-Pad4)") (class "Default")
      (node (ref "SV1") (pin "4") (pinfunction "4_4") (pintype "passive"))
    )
    (net (code "95") (name "unconnected-(SV1-Pad5)") (class "Default")
      (node (ref "SV1") (pin "5") (pinfunction "5_5") (pintype "passive"))
    )
    (net (code "96") (name "unconnected-(SV1-Pad6)") (class "Default")
      (node (ref "SV1") (pin "6") (pinfunction "6_6") (pintype "passive"))
    )
    (net (code "97") (name "unconnected-(SV1-Pad7)") (class "Default")
      (node (ref "SV1") (pin "7") (pinfunction "7_7") (pintype "passive"))
    )
    (net (code "98") (name "unconnected-(SV1-Pad8)") (class "Default")
      (node (ref "SV1") (pin "8") (pinfunction "8_8") (pintype "passive"))
    )
    (net (code "99") (name "unconnected-(SV1-Pad10)") (class "Default")
      (node (ref "SV1") (pin "10") (pinfunction "10_10") (pintype "passive"))
    )
    (net (code "100") (name "unconnected-(SV1-Pad12)") (class "Default")
      (node (ref "SV1") (pin "12") (pinfunction "12_12") (pintype "passive"))
    )
    (net (code "101") (name "unconnected-(SV1-Pad13)") (class "Default")
      (node (ref "SV1") (pin "13") (pinfunction "13_13") (pintype "passive"))
    )
    (net (code "102") (name "unconnected-(SV1-Pad14)") (class "Default")
      (node (ref "SV1") (pin "14") (pinfunction "14_14") (pintype "passive"))
    )
    (net (code "103") (name "unconnected-(SV1-Pad15)") (class "Default")
      (node (ref "SV1") (pin "15") (pinfunction "15_15") (pintype "passive"))
    )
    (net (code "104") (name "unconnected-(SV1-Pad16)") (class "Default")
      (node (ref "SV1") (pin "16") (pinfunction "16_16") (pintype "passive"))
    )
    (net (code "105") (name "unconnected-(SV1-Pad17)") (class "Default")
      (node (ref "SV1") (pin "17") (pinfunction "17_17") (pintype "passive"))
    )
    (net (code "106") (name "unconnected-(SV1-Pad18)") (class "Default")
      (node (ref "SV1") (pin "18") (pinfunction "18_18") (pintype "passive"))
    )
    (net (code "107") (name "unconnected-(SV1-Pad19)") (class "Default")
      (node (ref "SV1") (pin "19") (pinfunction "19_19") (pintype "passive"))
    )
    (net (code "108") (name "unconnected-(SV1-Pad20)") (class "Default")
      (node (ref "SV1") (pin "20") (pinfunction "20_20") (pintype "passive"))
    )
    (net (code "109") (name "unconnected-(SV1-Pad21)") (class "Default")
      (node (ref "SV1") (pin "21") (pinfunction "21_21") (pintype "passive"))
    )
    (net (code "110") (name "unconnected-(SV1-Pad22)") (class "Default")
      (node (ref "SV1") (pin "22") (pinfunction "22_22") (pintype "passive"))
    )
    (net (code "111") (name "unconnected-(SV1-Pad23)") (class "Default")
      (node (ref "SV1") (pin "23") (pinfunction "23_23") (pintype "passive"))
    )
    (net (code "112") (name "unconnected-(SV1-Pad24)") (class "Default")
      (node (ref "SV1") (pin "24") (pinfunction "24_24") (pintype "passive"))
    )
    (net (code "113") (name "unconnected-(X4A-S-Pad1)") (class "Default")
      (node (ref "X4") (pin "1") (pinfunction "S_1") (pintype "passive"))
    )
  )
)
